# USB_C.net
KiCad netlist of a schematic drawn in Altium Designer
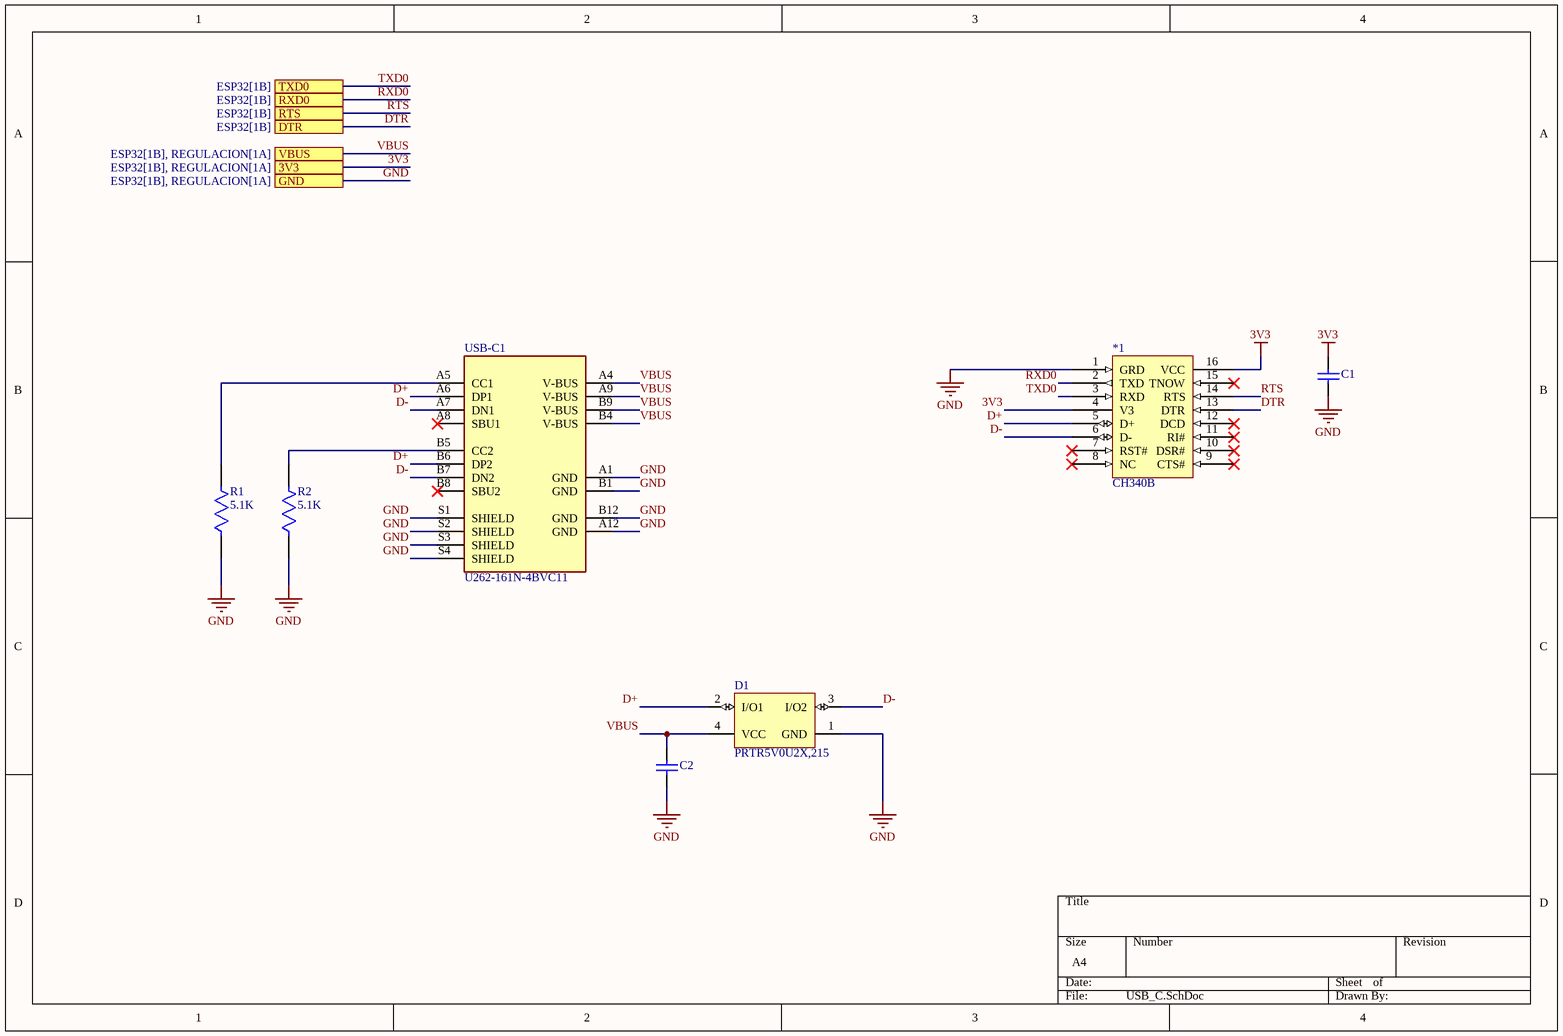
[diagram p0: USB_C.SchDoc]

(export (version "E")
  (design (tool "Eeschema 10.0.6"))
  (components
    (comp (ref "*1")
      (value "CH340B")
      (footprint "CH340B")
      (description "- USB 2.0 Transceiver 2Mbps SOP-16_150mil USB ICs ROHS")
      (libsource (lib "Isidro_Library") (part "CH340B"))
    )
    (comp (ref "C1")
      (value "08055C104KAT2A")
      (footprint "CAPC2013X94X50ML20T25")
      (description "Chip Capacitor, Ceramic, 0.1 uF, 10%, 50 V, 0805, RoHS, Tape and Reel")
      (fields (field (name "MANUFACTURER") "AVX"))
      (libsource (lib "Altium Content Vault") (part "CAP-NP-2"))
    )
    (comp (ref "C2")
      (value "08055C104KAT2A")
      (footprint "CAPC2013X94X50ML20T25")
      (description "Chip Capacitor, Ceramic, 0.1 uF, 10%, 50 V, 0805, RoHS, Tape and Reel")
      (fields (field (name "MANUFACTURER") "AVX"))
      (libsource (lib "Altium Content Vault") (part "CAP-NP-2"))
    )
    (comp (ref "D1")
      (value "PRTR5V0U2X,215")
      (footprint "NXP-SOT143B-4_V")
      (fields (field (name "MANUFACTURER") "NXP Semiconductors"))
      (libsource (lib "Altium Content Vault") (part "NXP-PRTR5V0U2X,215-4"))
    )
    (comp (ref "R1")
      (value "5.1K")
      (footprint "FP-CRCW0805-e3-MFG")
      (description "RES Thick Film, 5.1kΩ, 1%, 0.125W, 100ppm/°C, 0805")
      (fields (field (name "TOLERANCE") "1%"))
      (libsource (lib "Altium Content Vault") (part "1029c3af85768c4190bb7ad29bc67b5"))
    )
    (comp (ref "R2")
      (value "5.1K")
      (footprint "FP-CRCW0805-e3-MFG")
      (description "RES Thick Film, 5.1kΩ, 1%, 0.125W, 100ppm/°C, 0805")
      (fields (field (name "TOLERANCE") "1%"))
      (libsource (lib "Altium Content Vault") (part "1029c3af85768c4190bb7ad29bc67b5"))
    )
    (comp (ref "USB-C1")
      (value "U262-161N-4BVC11")
      (footprint "U262-161N-4BVC11")
      (description "USB - Type C Female 16 SMT USB Connectors RoHS")
      (libsource (lib "AQIMon") (part "U262-161N-4BVC11"))
    )
  )
  (nets
    (net (code "1") (name "/D+") (class "Default")
      (node (ref "*1") (pin "5") (pinfunction "D+_5") (pintype "bidirectional"))
      (node (ref "D1") (pin "2") (pinfunction "I/O1_2") (pintype "bidirectional"))
      (node (ref "USB-C1") (pin "A6") (pinfunction "DP1_A6") (pintype "power_in"))
      (node (ref "USB-C1") (pin "B6") (pinfunction "DP2_B6") (pintype "power_in"))
    )
    (net (code "2") (name "/D-") (class "Default")
      (node (ref "*1") (pin "6") (pinfunction "D-_6") (pintype "bidirectional"))
      (node (ref "D1") (pin "3") (pinfunction "I/O2_3") (pintype "bidirectional"))
      (node (ref "USB-C1") (pin "A7") (pinfunction "DN1_A7") (pintype "power_in"))
      (node (ref "USB-C1") (pin "B7") (pinfunction "DN2_B7") (pintype "power_in"))
    )
    (net (code "3") (name "/DTR") (class "Default")
      (node (ref "*1") (pin "13") (pinfunction "DTR_13") (pintype "input"))
    )
    (net (code "4") (name "/RTS") (class "Default")
      (node (ref "*1") (pin "14") (pinfunction "RTS_14") (pintype "input"))
    )
    (net (code "5") (name "/RXD0") (class "Default")
      (node (ref "*1") (pin "2") (pinfunction "TXD_2") (pintype "output"))
    )
    (net (code "6") (name "/TXD0") (class "Default")
      (node (ref "*1") (pin "3") (pinfunction "RXD_3") (pintype "input"))
    )
    (net (code "7") (name "/VBUS") (class "Default")
      (node (ref "C2") (pin "2") (pinfunction "2_2") (pintype "passive"))
      (node (ref "D1") (pin "4") (pinfunction "VCC_4") (pintype "power_in"))
      (node (ref "USB-C1") (pin "A4") (pinfunction "V-BUS_A4") (pintype "power_in"))
      (node (ref "USB-C1") (pin "A9") (pinfunction "V-BUS_A9") (pintype "power_in"))
      (node (ref "USB-C1") (pin "B4") (pinfunction "V-BUS_B4") (pintype "power_in"))
      (node (ref "USB-C1") (pin "B9") (pinfunction "V-BUS_B9") (pintype "power_in"))
    )
    (net (code "8") (name "3V3") (class "Default")
      (node (ref "*1") (pin "16") (pinfunction "VCC_16") (pintype "power_in"))
      (node (ref "*1") (pin "4") (pinfunction "V3_4") (pintype "power_in"))
      (node (ref "C1") (pin "2") (pinfunction "2_2") (pintype "passive"))
    )
    (net (code "9") (name "GND") (class "Default")
      (node (ref "*1") (pin "1") (pinfunction "GRD_1") (pintype "input"))
      (node (ref "C1") (pin "1") (pinfunction "1_1") (pintype "passive"))
      (node (ref "C2") (pin "1") (pinfunction "1_1") (pintype "passive"))
      (node (ref "D1") (pin "1") (pinfunction "GND_1") (pintype "power_in"))
      (node (ref "R1") (pin "1") (pinfunction "1_1") (pintype "passive"))
      (node (ref "R2") (pin "1") (pinfunction "1_1") (pintype "passive"))
      (node (ref "USB-C1") (pin "A1") (pinfunction "GND_A1") (pintype "power_in"))
      (node (ref "USB-C1") (pin "A12") (pinfunction "GND_A12") (pintype "power_in"))
      (node (ref "USB-C1") (pin "B1") (pinfunction "GND_B1") (pintype "power_in"))
      (node (ref "USB-C1") (pin "B12") (pinfunction "GND_B12") (pintype "power_in"))
      (node (ref "USB-C1") (pin "S1") (pinfunction "SHIELD_S1") (pintype "passive"))
      (node (ref "USB-C1") (pin "S2") (pinfunction "SHIELD_S2") (pintype "passive"))
      (node (ref "USB-C1") (pin "S3") (pinfunction "SHIELD_S3") (pintype "passive"))
      (node (ref "USB-C1") (pin "S4") (pinfunction "SHIELD_S4") (pintype "passive"))
    )
    (net (code "10") (name "Net-(USB-C1-CC1)") (class "Default")
      (node (ref "R1") (pin "2") (pinfunction "2_2") (pintype "passive"))
      (node (ref "USB-C1") (pin "A5") (pinfunction "CC1_A5") (pintype "power_in"))
    )
    (net (code "11") (name "Net-(USB-C1-CC2)") (class "Default")
      (node (ref "R2") (pin "2") (pinfunction "2_2") (pintype "passive"))
      (node (ref "USB-C1") (pin "B5") (pinfunction "CC2_B5") (pintype "power_in"))
    )
    (net (code "12") (name "unconnected-(*1-CTS#-Pad9)") (class "Default")
      (node (ref "*1") (pin "9") (pinfunction "CTS#_9") (pintype "input+no_connect"))
    )
    (net (code "13") (name "unconnected-(*1-DCD-Pad12)") (class "Default")
      (node (ref "*1") (pin "12") (pinfunction "DCD_12") (pintype "input+no_connect"))
    )
    (net (code "14") (name "unconnected-(*1-DSR#-Pad10)") (class "Default")
      (node (ref "*1") (pin "10") (pinfunction "DSR#_10") (pintype "input+no_connect"))
    )
    (net (code "15") (name "unconnected-(*1-NC-Pad8)") (class "Default")
      (node (ref "*1") (pin "8") (pinfunction "NC_8") (pintype "input+no_connect"))
    )
    (net (code "16") (name "unconnected-(*1-RI#-Pad11)") (class "Default")
      (node (ref "*1") (pin "11") (pinfunction "RI#_11") (pintype "input+no_connect"))
    )
    (net (code "17") (name "unconnected-(*1-RST#-Pad7)") (class "Default")
      (node (ref "*1") (pin "7") (pinfunction "RST#_7") (pintype "input+no_connect"))
    )
    (net (code "18") (name "unconnected-(*1-TNOW-Pad15)") (class "Default")
      (node (ref "*1") (pin "15") (pinfunction "TNOW_15") (pintype "input+no_connect"))
    )
    (net (code "19") (name "unconnected-(USB-C1-SBU1-PadA8)") (class "Default")
      (node (ref "USB-C1") (pin "A8") (pinfunction "SBU1_A8") (pintype "power_in+no_connect"))
    )
    (net (code "20") (name "unconnected-(USB-C1-SBU2-PadB8)") (class "Default")
      (node (ref "USB-C1") (pin "B8") (pinfunction "SBU2_B8") (pintype "power_in+no_connect"))
    )
  )
)
